# 08_FPGA_banks_3_4_5.net
KiCad netlist of a schematic drawn in Altium Designer
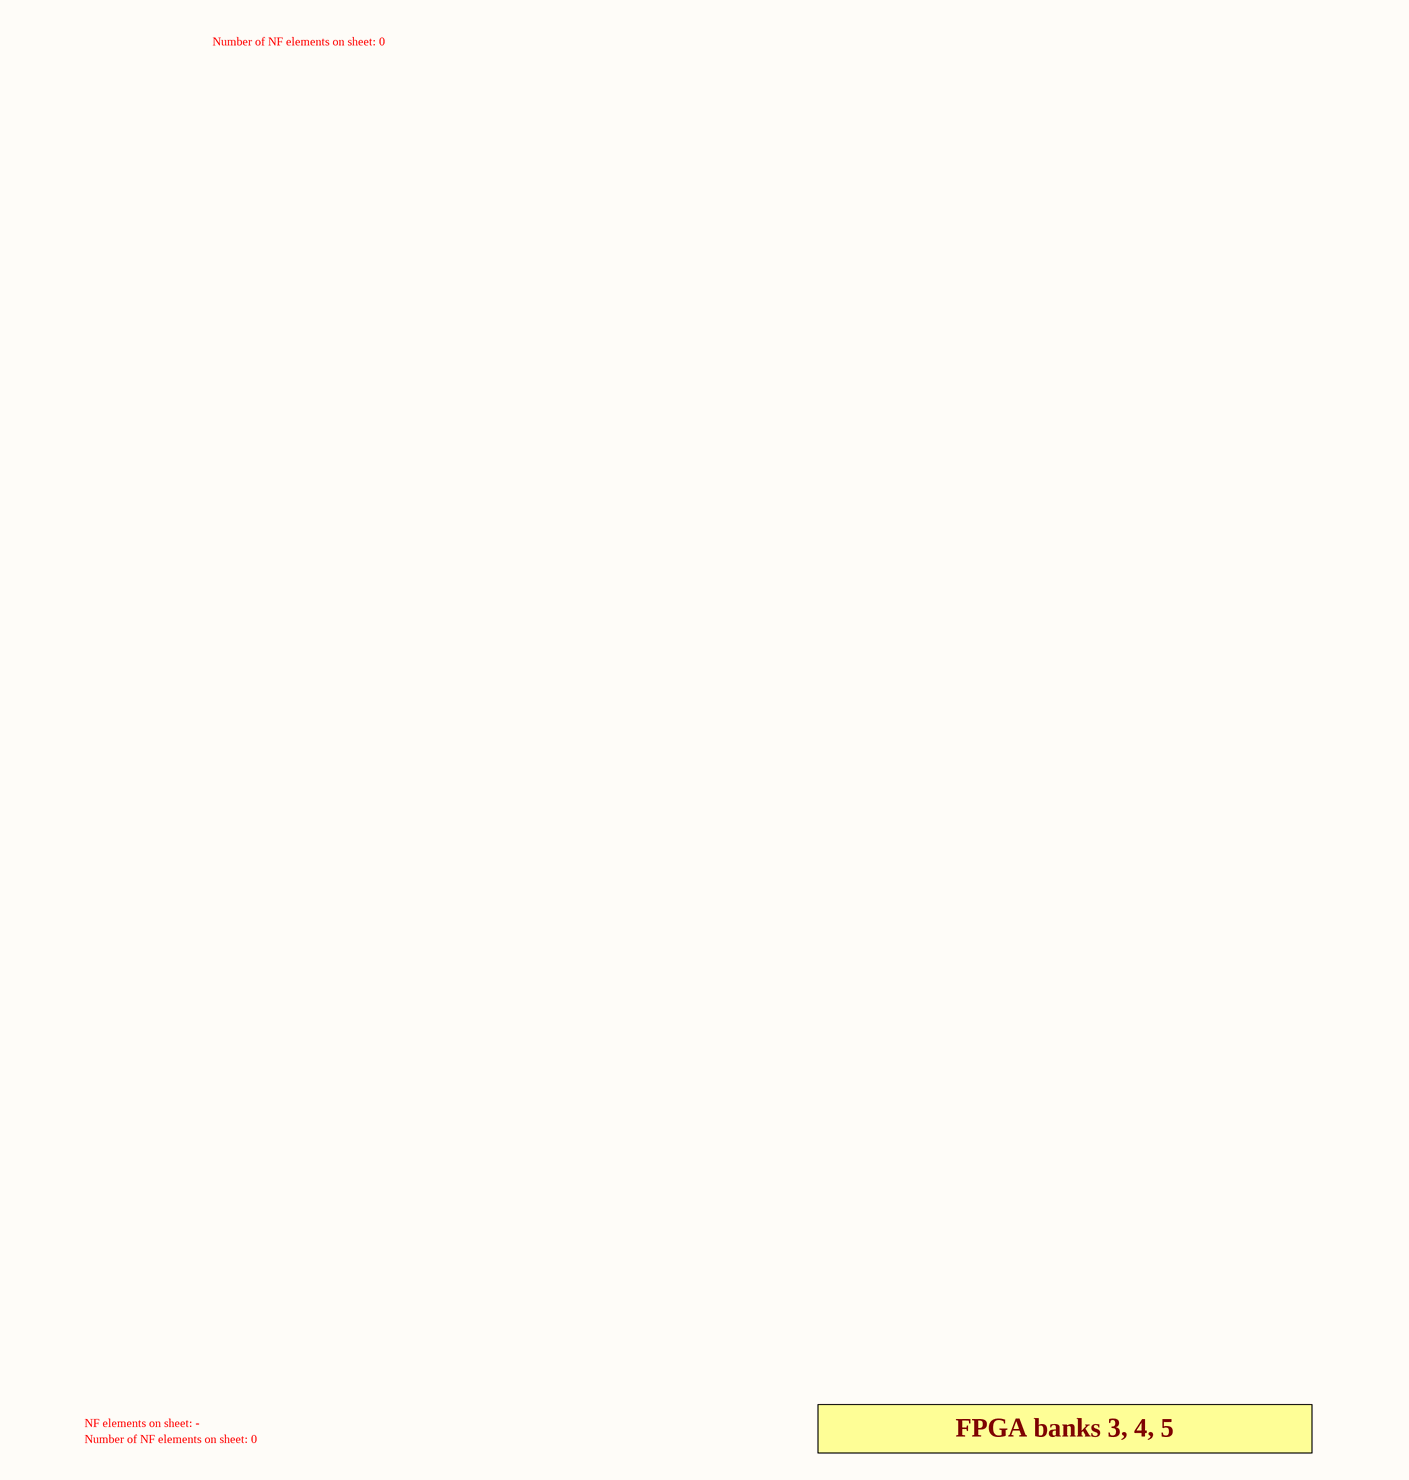
[diagram p0: 08_FPGA_banks_3_4_5.SchDoc, top]
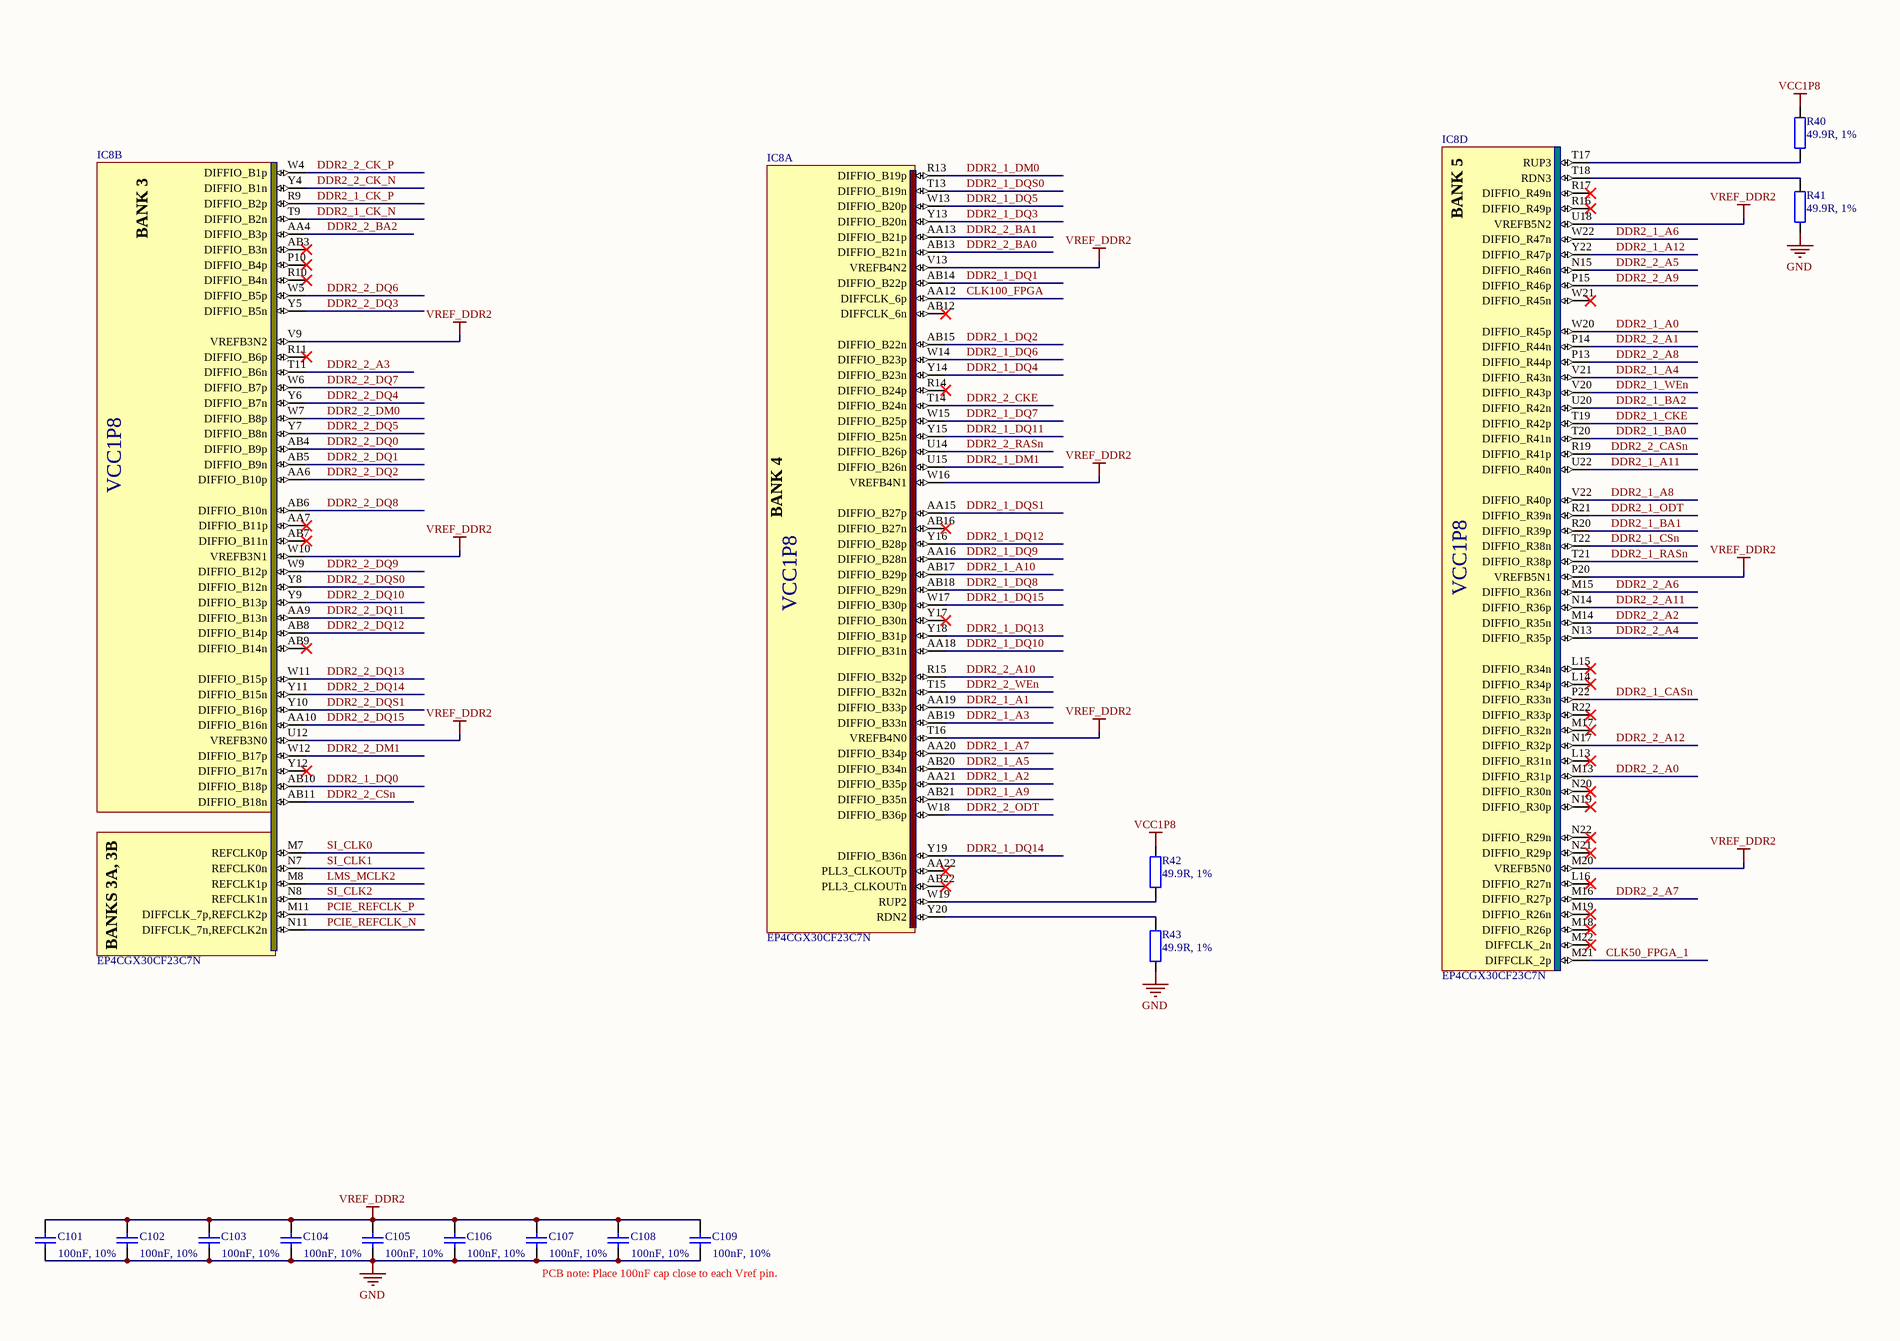
[diagram p1: 08_FPGA_banks_3_4_5.SchDoc, bottom]

(export (version "E")
  (design (tool "Eeschema 10.0.6"))
  (components
    (comp (ref "C101")
      (value "100nF, 10%")
      (footprint "CAP0402")
      (fields
        (field (name "TOLERANCE") "10 %")
        (field (name "MANUFACTURER") "Murata Electronics")
        (field (name "MANUFACTURER PART NUMBER") "GRM155R71C104KA88D")
      )
      (libsource (lib "LimeFPGAboard_schLib") (part "Cap_0603"))
    )
    (comp (ref "C102")
      (value "100nF, 10%")
      (footprint "CAP0402")
      (fields
        (field (name "TOLERANCE") "10 %")
        (field (name "MANUFACTURER") "Murata Electronics")
        (field (name "MANUFACTURER PART NUMBER") "GRM155R71C104KA88D")
      )
      (libsource (lib "LimeFPGAboard_schLib") (part "Cap_0603"))
    )
    (comp (ref "C103")
      (value "100nF, 10%")
      (footprint "CAP0402")
      (fields
        (field (name "TOLERANCE") "10 %")
        (field (name "MANUFACTURER") "Murata Electronics")
        (field (name "MANUFACTURER PART NUMBER") "GRM155R71C104KA88D")
      )
      (libsource (lib "LimeFPGAboard_schLib") (part "Cap_0603"))
    )
    (comp (ref "C104")
      (value "100nF, 10%")
      (footprint "CAP0402")
      (fields
        (field (name "TOLERANCE") "10 %")
        (field (name "MANUFACTURER") "Murata Electronics")
        (field (name "MANUFACTURER PART NUMBER") "GRM155R71C104KA88D")
      )
      (libsource (lib "LimeFPGAboard_schLib") (part "Cap_0603"))
    )
    (comp (ref "C105")
      (value "100nF, 10%")
      (footprint "CAP0402")
      (fields
        (field (name "TOLERANCE") "10 %")
        (field (name "MANUFACTURER") "Murata Electronics")
        (field (name "MANUFACTURER PART NUMBER") "GRM155R71C104KA88D")
      )
      (libsource (lib "LimeFPGAboard_schLib") (part "Cap_0603"))
    )
    (comp (ref "C106")
      (value "100nF, 10%")
      (footprint "CAP0402")
      (fields
        (field (name "TOLERANCE") "10 %")
        (field (name "MANUFACTURER") "Murata Electronics")
        (field (name "MANUFACTURER PART NUMBER") "GRM155R71C104KA88D")
      )
      (libsource (lib "LimeFPGAboard_schLib") (part "Cap_0603"))
    )
    (comp (ref "C107")
      (value "100nF, 10%")
      (footprint "CAP0402")
      (fields
        (field (name "TOLERANCE") "10 %")
        (field (name "MANUFACTURER") "Murata Electronics")
        (field (name "MANUFACTURER PART NUMBER") "GRM155R71C104KA88D")
      )
      (libsource (lib "LimeFPGAboard_schLib") (part "Cap_0603"))
    )
    (comp (ref "C108")
      (value "100nF, 10%")
      (footprint "CAP0402")
      (fields
        (field (name "TOLERANCE") "10 %")
        (field (name "MANUFACTURER") "Murata Electronics")
        (field (name "MANUFACTURER PART NUMBER") "GRM155R71C104KA88D")
      )
      (libsource (lib "LimeFPGAboard_schLib") (part "Cap_0603"))
    )
    (comp (ref "C109")
      (value "100nF, 10%")
      (footprint "CAP0402")
      (fields
        (field (name "TOLERANCE") "10 %")
        (field (name "MANUFACTURER") "Murata Electronics")
        (field (name "MANUFACTURER PART NUMBER") "GRM155R71C104KA88D")
      )
      (libsource (lib "LimeFPGAboard_schLib") (part "Cap_0603"))
    )
    (comp (ref "IC8")
      (value "EP4CGX30CF23C7N")
      (footprint "ALTR-FBGA484_A-200")
      (fields (field (name "MANUFACTURER") "Altera"))
      (libsource (lib "LimeMicroAltiumLib_schLib") (part "EP4CGX30CF23C7N"))
    )
    (comp (ref "R40")
      (value "49.9R, 1%")
      (footprint "RES0402")
      (fields
        (field (name "TOLERANCE") "±1%")
        (field (name "MANUFACTURER") "Samsung Electro-Mechanics America, Inc.")
        (field (name "MANUFACTURER PART NUMBER") "RC1005F49R9CS")
      )
      (libsource (lib "LimeMicroAltiumLib_schLib") (part "Res_0402"))
    )
    (comp (ref "R41")
      (value "49.9R, 1%")
      (footprint "RES0402")
      (fields
        (field (name "TOLERANCE") "±1%")
        (field (name "MANUFACTURER") "Samsung Electro-Mechanics America, Inc.")
        (field (name "MANUFACTURER PART NUMBER") "RC1005F49R9CS")
      )
      (libsource (lib "LimeMicroAltiumLib_schLib") (part "Res_0402"))
    )
    (comp (ref "R42")
      (value "49.9R, 1%")
      (footprint "RES0402")
      (fields
        (field (name "TOLERANCE") "±1%")
        (field (name "MANUFACTURER") "Samsung Electro-Mechanics America, Inc.")
        (field (name "MANUFACTURER PART NUMBER") "RC1005F49R9CS")
      )
      (libsource (lib "LimeMicroAltiumLib_schLib") (part "Res_0402"))
    )
    (comp (ref "R43")
      (value "49.9R, 1%")
      (footprint "RES0402")
      (fields
        (field (name "TOLERANCE") "±1%")
        (field (name "MANUFACTURER") "Samsung Electro-Mechanics America, Inc.")
        (field (name "MANUFACTURER PART NUMBER") "RC1005F49R9CS")
      )
      (libsource (lib "LimeMicroAltiumLib_schLib") (part "Res_0402"))
    )
  )
  (nets
    (net (code "1") (name "/CLK50_FPGA_1") (class "Default")
      (node (ref "IC8") (pin "M21") (pinfunction "DIFFCLK_2p_M21") (pintype "bidirectional"))
    )
    (net (code "2") (name "/CLK100_FPGA") (class "Default")
      (node (ref "IC8") (pin "AA12") (pinfunction "DIFFCLK_6p_AA12") (pintype "bidirectional"))
    )
    (net (code "3") (name "/DDR2_1_A0") (class "Default")
      (node (ref "IC8") (pin "W20") (pinfunction "DIFFIO_R45p_W20") (pintype "bidirectional"))
    )
    (net (code "4") (name "/DDR2_1_A1") (class "Default")
      (node (ref "IC8") (pin "AA19") (pinfunction "DIFFIO_B33p_AA19") (pintype "bidirectional"))
    )
    (net (code "5") (name "/DDR2_1_A2") (class "Default")
      (node (ref "IC8") (pin "AA21") (pinfunction "DIFFIO_B35p_AA21") (pintype "bidirectional"))
    )
    (net (code "6") (name "/DDR2_1_A3") (class "Default")
      (node (ref "IC8") (pin "AB19") (pinfunction "DIFFIO_B33n_AB19") (pintype "bidirectional"))
    )
    (net (code "7") (name "/DDR2_1_A4") (class "Default")
      (node (ref "IC8") (pin "V21") (pinfunction "DIFFIO_R43n_V21") (pintype "bidirectional"))
    )
    (net (code "8") (name "/DDR2_1_A5") (class "Default")
      (node (ref "IC8") (pin "AB20") (pinfunction "DIFFIO_B34n_AB20") (pintype "bidirectional"))
    )
    (net (code "9") (name "/DDR2_1_A6") (class "Default")
      (node (ref "IC8") (pin "W22") (pinfunction "DIFFIO_R47n_W22") (pintype "bidirectional"))
    )
    (net (code "10") (name "/DDR2_1_A7") (class "Default")
      (node (ref "IC8") (pin "AA20") (pinfunction "DIFFIO_B34p_AA20") (pintype "bidirectional"))
    )
    (net (code "11") (name "/DDR2_1_A8") (class "Default")
      (node (ref "IC8") (pin "V22") (pinfunction "DIFFIO_R40p_V22") (pintype "bidirectional"))
    )
    (net (code "12") (name "/DDR2_1_A9") (class "Default")
      (node (ref "IC8") (pin "AB21") (pinfunction "DIFFIO_B35n_AB21") (pintype "bidirectional"))
    )
    (net (code "13") (name "/DDR2_1_A10") (class "Default")
      (node (ref "IC8") (pin "AB17") (pinfunction "DIFFIO_B29p_AB17") (pintype "bidirectional"))
    )
    (net (code "14") (name "/DDR2_1_A11") (class "Default")
      (node (ref "IC8") (pin "U22") (pinfunction "DIFFIO_R40n_U22") (pintype "bidirectional"))
    )
    (net (code "15") (name "/DDR2_1_A12") (class "Default")
      (node (ref "IC8") (pin "Y22") (pinfunction "DIFFIO_R47p_Y22") (pintype "bidirectional"))
    )
    (net (code "16") (name "/DDR2_1_BA0") (class "Default")
      (node (ref "IC8") (pin "T20") (pinfunction "DIFFIO_R41n_T20") (pintype "bidirectional"))
    )
    (net (code "17") (name "/DDR2_1_BA1") (class "Default")
      (node (ref "IC8") (pin "R20") (pinfunction "DIFFIO_R39p_R20") (pintype "bidirectional"))
    )
    (net (code "18") (name "/DDR2_1_BA2") (class "Default")
      (node (ref "IC8") (pin "U20") (pinfunction "DIFFIO_R42n_U20") (pintype "bidirectional"))
    )
    (net (code "19") (name "/DDR2_1_CASn") (class "Default")
      (node (ref "IC8") (pin "P22") (pinfunction "DIFFIO_R33n_P22") (pintype "bidirectional"))
    )
    (net (code "20") (name "/DDR2_1_CKE") (class "Default")
      (node (ref "IC8") (pin "T19") (pinfunction "DIFFIO_R42p_T19") (pintype "bidirectional"))
    )
    (net (code "21") (name "/DDR2_1_CK_N") (class "Default")
      (node (ref "IC8") (pin "T9") (pinfunction "DIFFIO_B2n_T9") (pintype "bidirectional"))
    )
    (net (code "22") (name "/DDR2_1_CK_P") (class "Default")
      (node (ref "IC8") (pin "R9") (pinfunction "DIFFIO_B2p_R9") (pintype "bidirectional"))
    )
    (net (code "23") (name "/DDR2_1_CSn") (class "Default")
      (node (ref "IC8") (pin "T22") (pinfunction "DIFFIO_R38n_T22") (pintype "bidirectional"))
    )
    (net (code "24") (name "/DDR2_1_DM0") (class "Default")
      (node (ref "IC8") (pin "R13") (pinfunction "DIFFIO_B19p_R13") (pintype "bidirectional"))
    )
    (net (code "25") (name "/DDR2_1_DM1") (class "Default")
      (node (ref "IC8") (pin "U15") (pinfunction "DIFFIO_B26n_U15") (pintype "bidirectional"))
    )
    (net (code "26") (name "/DDR2_1_DQ0") (class "Default")
      (node (ref "IC8") (pin "AB10") (pinfunction "DIFFIO_B18p_AB10") (pintype "bidirectional"))
    )
    (net (code "27") (name "/DDR2_1_DQ1") (class "Default")
      (node (ref "IC8") (pin "AB14") (pinfunction "DIFFIO_B22p_AB14") (pintype "bidirectional"))
    )
    (net (code "28") (name "/DDR2_1_DQ2") (class "Default")
      (node (ref "IC8") (pin "AB15") (pinfunction "DIFFIO_B22n_AB15") (pintype "bidirectional"))
    )
    (net (code "29") (name "/DDR2_1_DQ3") (class "Default")
      (node (ref "IC8") (pin "Y13") (pinfunction "DIFFIO_B20n_Y13") (pintype "bidirectional"))
    )
    (net (code "30") (name "/DDR2_1_DQ4") (class "Default")
      (node (ref "IC8") (pin "Y14") (pinfunction "DIFFIO_B23n_Y14") (pintype "bidirectional"))
    )
    (net (code "31") (name "/DDR2_1_DQ5") (class "Default")
      (node (ref "IC8") (pin "W13") (pinfunction "DIFFIO_B20p_W13") (pintype "bidirectional"))
    )
    (net (code "32") (name "/DDR2_1_DQ6") (class "Default")
      (node (ref "IC8") (pin "W14") (pinfunction "DIFFIO_B23p_W14") (pintype "bidirectional"))
    )
    (net (code "33") (name "/DDR2_1_DQ7") (class "Default")
      (node (ref "IC8") (pin "W15") (pinfunction "DIFFIO_B25p_W15") (pintype "bidirectional"))
    )
    (net (code "34") (name "/DDR2_1_DQ8") (class "Default")
      (node (ref "IC8") (pin "AB18") (pinfunction "DIFFIO_B29n_AB18") (pintype "bidirectional"))
    )
    (net (code "35") (name "/DDR2_1_DQ9") (class "Default")
      (node (ref "IC8") (pin "AA16") (pinfunction "DIFFIO_B28n_AA16") (pintype "bidirectional"))
    )
    (net (code "36") (name "/DDR2_1_DQ10") (class "Default")
      (node (ref "IC8") (pin "AA18") (pinfunction "DIFFIO_B31n_AA18") (pintype "bidirectional"))
    )
    (net (code "37") (name "/DDR2_1_DQ11") (class "Default")
      (node (ref "IC8") (pin "Y15") (pinfunction "DIFFIO_B25n_Y15") (pintype "bidirectional"))
    )
    (net (code "38") (name "/DDR2_1_DQ12") (class "Default")
      (node (ref "IC8") (pin "Y16") (pinfunction "DIFFIO_B28p_Y16") (pintype "bidirectional"))
    )
    (net (code "39") (name "/DDR2_1_DQ13") (class "Default")
      (node (ref "IC8") (pin "Y18") (pinfunction "DIFFIO_B31p_Y18") (pintype "bidirectional"))
    )
    (net (code "40") (name "/DDR2_1_DQ14") (class "Default")
      (node (ref "IC8") (pin "Y19") (pinfunction "DIFFIO_B36n_Y19") (pintype "bidirectional"))
    )
    (net (code "41") (name "/DDR2_1_DQ15") (class "Default")
      (node (ref "IC8") (pin "W17") (pinfunction "DIFFIO_B30p_W17") (pintype "bidirectional"))
    )
    (net (code "42") (name "/DDR2_1_DQS0") (class "Default")
      (node (ref "IC8") (pin "T13") (pinfunction "DIFFIO_B19n_T13") (pintype "bidirectional"))
    )
    (net (code "43") (name "/DDR2_1_DQS1") (class "Default")
      (node (ref "IC8") (pin "AA15") (pinfunction "DIFFIO_B27p_AA15") (pintype "bidirectional"))
    )
    (net (code "44") (name "/DDR2_1_ODT") (class "Default")
      (node (ref "IC8") (pin "R21") (pinfunction "DIFFIO_R39n_R21") (pintype "bidirectional"))
    )
    (net (code "45") (name "/DDR2_1_RASn") (class "Default")
      (node (ref "IC8") (pin "T21") (pinfunction "DIFFIO_R38p_T21") (pintype "bidirectional"))
    )
    (net (code "46") (name "/DDR2_1_WEn") (class "Default")
      (node (ref "IC8") (pin "V20") (pinfunction "DIFFIO_R43p_V20") (pintype "bidirectional"))
    )
    (net (code "47") (name "/DDR2_2_A0") (class "Default")
      (node (ref "IC8") (pin "M13") (pinfunction "DIFFIO_R31p_M13") (pintype "bidirectional"))
    )
    (net (code "48") (name "/DDR2_2_A1") (class "Default")
      (node (ref "IC8") (pin "P14") (pinfunction "DIFFIO_R44n_P14") (pintype "bidirectional"))
    )
    (net (code "49") (name "/DDR2_2_A2") (class "Default")
      (node (ref "IC8") (pin "M14") (pinfunction "DIFFIO_R35n_M14") (pintype "bidirectional"))
    )
    (net (code "50") (name "/DDR2_2_A3") (class "Default")
      (node (ref "IC8") (pin "T11") (pinfunction "DIFFIO_B6n_T11") (pintype "bidirectional"))
    )
    (net (code "51") (name "/DDR2_2_A4") (class "Default")
      (node (ref "IC8") (pin "N13") (pinfunction "DIFFIO_R35p_N13") (pintype "bidirectional"))
    )
    (net (code "52") (name "/DDR2_2_A5") (class "Default")
      (node (ref "IC8") (pin "N15") (pinfunction "DIFFIO_R46n_N15") (pintype "bidirectional"))
    )
    (net (code "53") (name "/DDR2_2_A6") (class "Default")
      (node (ref "IC8") (pin "M15") (pinfunction "DIFFIO_R36n_M15") (pintype "bidirectional"))
    )
    (net (code "54") (name "/DDR2_2_A7") (class "Default")
      (node (ref "IC8") (pin "M16") (pinfunction "DIFFIO_R27p_M16") (pintype "bidirectional"))
    )
    (net (code "55") (name "/DDR2_2_A8") (class "Default")
      (node (ref "IC8") (pin "P13") (pinfunction "DIFFIO_R44p_P13") (pintype "bidirectional"))
    )
    (net (code "56") (name "/DDR2_2_A9") (class "Default")
      (node (ref "IC8") (pin "P15") (pinfunction "DIFFIO_R46p_P15") (pintype "bidirectional"))
    )
    (net (code "57") (name "/DDR2_2_A10") (class "Default")
      (node (ref "IC8") (pin "R15") (pinfunction "DIFFIO_B32p_R15") (pintype "bidirectional"))
    )
    (net (code "58") (name "/DDR2_2_A11") (class "Default")
      (node (ref "IC8") (pin "N14") (pinfunction "DIFFIO_R36p_N14") (pintype "bidirectional"))
    )
    (net (code "59") (name "/DDR2_2_A12") (class "Default")
      (node (ref "IC8") (pin "N17") (pinfunction "DIFFIO_R32p_N17") (pintype "bidirectional"))
    )
    (net (code "60") (name "/DDR2_2_BA0") (class "Default")
      (node (ref "IC8") (pin "AB13") (pinfunction "DIFFIO_B21n_AB13") (pintype "bidirectional"))
    )
    (net (code "61") (name "/DDR2_2_BA1") (class "Default")
      (node (ref "IC8") (pin "AA13") (pinfunction "DIFFIO_B21p_AA13") (pintype "bidirectional"))
    )
    (net (code "62") (name "/DDR2_2_BA2") (class "Default")
      (node (ref "IC8") (pin "AA4") (pinfunction "DIFFIO_B3p_AA4") (pintype "bidirectional"))
    )
    (net (code "63") (name "/DDR2_2_CASn") (class "Default")
      (node (ref "IC8") (pin "R19") (pinfunction "DIFFIO_R41p_R19") (pintype "bidirectional"))
    )
    (net (code "64") (name "/DDR2_2_CKE") (class "Default")
      (node (ref "IC8") (pin "T14") (pinfunction "DIFFIO_B24n_T14") (pintype "bidirectional"))
    )
    (net (code "65") (name "/DDR2_2_CK_N") (class "Default")
      (node (ref "IC8") (pin "Y4") (pinfunction "DIFFIO_B1n_Y4") (pintype "bidirectional"))
    )
    (net (code "66") (name "/DDR2_2_CK_P") (class "Default")
      (node (ref "IC8") (pin "W4") (pinfunction "DIFFIO_B1p_W4") (pintype "bidirectional"))
    )
    (net (code "67") (name "/DDR2_2_CSn") (class "Default")
      (node (ref "IC8") (pin "AB11") (pinfunction "DIFFIO_B18n_AB11") (pintype "bidirectional"))
    )
    (net (code "68") (name "/DDR2_2_DM0") (class "Default")
      (node (ref "IC8") (pin "W7") (pinfunction "DIFFIO_B8p_W7") (pintype "bidirectional"))
    )
    (net (code "69") (name "/DDR2_2_DM1") (class "Default")
      (node (ref "IC8") (pin "W12") (pinfunction "DIFFIO_B17p_W12") (pintype "bidirectional"))
    )
    (net (code "70") (name "/DDR2_2_DQ0") (class "Default")
      (node (ref "IC8") (pin "AB4") (pinfunction "DIFFIO_B9p_AB4") (pintype "bidirectional"))
    )
    (net (code "71") (name "/DDR2_2_DQ1") (class "Default")
      (node (ref "IC8") (pin "AB5") (pinfunction "DIFFIO_B9n_AB5") (pintype "bidirectional"))
    )
    (net (code "72") (name "/DDR2_2_DQ2") (class "Default")
      (node (ref "IC8") (pin "AA6") (pinfunction "DIFFIO_B10p_AA6") (pintype "bidirectional"))
    )
    (net (code "73") (name "/DDR2_2_DQ3") (class "Default")
      (node (ref "IC8") (pin "Y5") (pinfunction "DIFFIO_B5n_Y5") (pintype "bidirectional"))
    )
    (net (code "74") (name "/DDR2_2_DQ4") (class "Default")
      (node (ref "IC8") (pin "Y6") (pinfunction "DIFFIO_B7n_Y6") (pintype "bidirectional"))
    )
    (net (code "75") (name "/DDR2_2_DQ5") (class "Default")
      (node (ref "IC8") (pin "Y7") (pinfunction "DIFFIO_B8n_Y7") (pintype "bidirectional"))
    )
    (net (code "76") (name "/DDR2_2_DQ6") (class "Default")
      (node (ref "IC8") (pin "W5") (pinfunction "DIFFIO_B5p_W5") (pintype "bidirectional"))
    )
    (net (code "77") (name "/DDR2_2_DQ7") (class "Default")
      (node (ref "IC8") (pin "W6") (pinfunction "DIFFIO_B7p_W6") (pintype "bidirectional"))
    )
    (net (code "78") (name "/DDR2_2_DQ8") (class "Default")
      (node (ref "IC8") (pin "AB6") (pinfunction "DIFFIO_B10n_AB6") (pintype "bidirectional"))
    )
    (net (code "79") (name "/DDR2_2_DQ9") (class "Default")
      (node (ref "IC8") (pin "W9") (pinfunction "DIFFIO_B12p_W9") (pintype "bidirectional"))
    )
    (net (code "80") (name "/DDR2_2_DQ10") (class "Default")
      (node (ref "IC8") (pin "Y9") (pinfunction "DIFFIO_B13p_Y9") (pintype "bidirectional"))
    )
    (net (code "81") (name "/DDR2_2_DQ11") (class "Default")
      (node (ref "IC8") (pin "AA9") (pinfunction "DIFFIO_B13n_AA9") (pintype "bidirectional"))
    )
    (net (code "82") (name "/DDR2_2_DQ12") (class "Default")
      (node (ref "IC8") (pin "AB8") (pinfunction "DIFFIO_B14p_AB8") (pintype "bidirectional"))
    )
    (net (code "83") (name "/DDR2_2_DQ13") (class "Default")
      (node (ref "IC8") (pin "W11") (pinfunction "DIFFIO_B15p_W11") (pintype "bidirectional"))
    )
    (net (code "84") (name "/DDR2_2_DQ14") (class "Default")
      (node (ref "IC8") (pin "Y11") (pinfunction "DIFFIO_B15n_Y11") (pintype "bidirectional"))
    )
    (net (code "85") (name "/DDR2_2_DQ15") (class "Default")
      (node (ref "IC8") (pin "AA10") (pinfunction "DIFFIO_B16n_AA10") (pintype "bidirectional"))
    )
    (net (code "86") (name "/DDR2_2_DQS0") (class "Default")
      (node (ref "IC8") (pin "Y8") (pinfunction "DIFFIO_B12n_Y8") (pintype "bidirectional"))
    )
    (net (code "87") (name "/DDR2_2_DQS1") (class "Default")
      (node (ref "IC8") (pin "Y10") (pinfunction "DIFFIO_B16p_Y10") (pintype "bidirectional"))
    )
    (net (code "88") (name "/DDR2_2_ODT") (class "Default")
      (node (ref "IC8") (pin "W18") (pinfunction "DIFFIO_B36p_W18") (pintype "bidirectional"))
    )
    (net (code "89") (name "/DDR2_2_RASn") (class "Default")
      (node (ref "IC8") (pin "U14") (pinfunction "DIFFIO_B26p_U14") (pintype "bidirectional"))
    )
    (net (code "90") (name "/DDR2_2_WEn") (class "Default")
      (node (ref "IC8") (pin "T15") (pinfunction "DIFFIO_B32n_T15") (pintype "bidirectional"))
    )
    (net (code "91") (name "/LMS_MCLK2") (class "Default")
      (node (ref "IC8") (pin "M8") (pinfunction "REFCLK1p_M8") (pintype "bidirectional"))
    )
    (net (code "92") (name "/PCIE_REFCLK_N") (class "Default")
      (node (ref "IC8") (pin "N11") (pinfunction "DIFFCLK_7n,REFCLK2n_N11") (pintype "bidirectional"))
    )
    (net (code "93") (name "/PCIE_REFCLK_P") (class "Default")
      (node (ref "IC8") (pin "M11") (pinfunction "DIFFCLK_7p,REFCLK2p_M11") (pintype "bidirectional"))
    )
    (net (code "94") (name "/SI_CLK0") (class "Default")
      (node (ref "IC8") (pin "M7") (pinfunction "REFCLK0p_M7") (pintype "bidirectional"))
    )
    (net (code "95") (name "/SI_CLK1") (class "Default")
      (node (ref "IC8") (pin "N7") (pinfunction "REFCLK0n_N7") (pintype "bidirectional"))
    )
    (net (code "96") (name "/SI_CLK2") (class "Default")
      (node (ref "IC8") (pin "N8") (pinfunction "REFCLK1n_N8") (pintype "bidirectional"))
    )
    (net (code "97") (name "GND") (class "Default")
      (node (ref "C101") (pin "2") (pinfunction "2_2") (pintype "passive"))
      (node (ref "C102") (pin "2") (pinfunction "2_2") (pintype "passive"))
      (node (ref "C103") (pin "2") (pinfunction "2_2") (pintype "passive"))
      (node (ref "C104") (pin "2") (pinfunction "2_2") (pintype "passive"))
      (node (ref "C105") (pin "2") (pinfunction "2_2") (pintype "passive"))
      (node (ref "C106") (pin "2") (pinfunction "2_2") (pintype "passive"))
      (node (ref "C107") (pin "2") (pinfunction "2_2") (pintype "passive"))
      (node (ref "C108") (pin "2") (pinfunction "2_2") (pintype "passive"))
      (node (ref "C109") (pin "2") (pinfunction "2_2") (pintype "passive"))
      (node (ref "R41") (pin "1") (pinfunction "1_1") (pintype "passive"))
      (node (ref "R43") (pin "1") (pinfunction "1_1") (pintype "passive"))
    )
    (net (code "98") (name "Net-(IC8A-RDN2)") (class "Default")
      (node (ref "IC8") (pin "Y20") (pinfunction "RDN2_Y20") (pintype "bidirectional"))
      (node (ref "R43") (pin "2") (pinfunction "2_2") (pintype "passive"))
    )
    (net (code "99") (name "Net-(IC8A-RUP2)") (class "Default")
      (node (ref "IC8") (pin "W19") (pinfunction "RUP2_W19") (pintype "bidirectional"))
      (node (ref "R42") (pin "1") (pinfunction "1_1") (pintype "passive"))
    )
    (net (code "100") (name "Net-(IC8D-RDN3)") (class "Default")
      (node (ref "IC8") (pin "T18") (pinfunction "RDN3_T18") (pintype "bidirectional"))
      (node (ref "R41") (pin "2") (pinfunction "2_2") (pintype "passive"))
    )
    (net (code "101") (name "Net-(IC8D-RUP3)") (class "Default")
      (node (ref "IC8") (pin "T17") (pinfunction "RUP3_T17") (pintype "bidirectional"))
      (node (ref "R40") (pin "1") (pinfunction "1_1") (pintype "passive"))
    )
    (net (code "102") (name "VCC1P8") (class "Default")
      (node (ref "R40") (pin "2") (pinfunction "2_2") (pintype "passive"))
      (node (ref "R42") (pin "2") (pinfunction "2_2") (pintype "passive"))
    )
    (net (code "103") (name "VREF_DDR2") (class "Default")
      (node (ref "C101") (pin "1") (pinfunction "1_1") (pintype "passive"))
      (node (ref "C102") (pin "1") (pinfunction "1_1") (pintype "passive"))
      (node (ref "C103") (pin "1") (pinfunction "1_1") (pintype "passive"))
      (node (ref "C104") (pin "1") (pinfunction "1_1") (pintype "passive"))
      (node (ref "C105") (pin "1") (pinfunction "1_1") (pintype "passive"))
      (node (ref "C106") (pin "1") (pinfunction "1_1") (pintype "passive"))
      (node (ref "C107") (pin "1") (pinfunction "1_1") (pintype "passive"))
      (node (ref "C108") (pin "1") (pinfunction "1_1") (pintype "passive"))
      (node (ref "C109") (pin "1") (pinfunction "1_1") (pintype "passive"))
      (node (ref "IC8") (pin "M20") (pinfunction "VREFB5N0_M20") (pintype "bidirectional"))
      (node (ref "IC8") (pin "P20") (pinfunction "VREFB5N1_P20") (pintype "bidirectional"))
      (node (ref "IC8") (pin "T16") (pinfunction "VREFB4N0_T16") (pintype "bidirectional"))
      (node (ref "IC8") (pin "U12") (pinfunction "VREFB3N0_U12") (pintype "bidirectional"))
      (node (ref "IC8") (pin "U18") (pinfunction "VREFB5N2_U18") (pintype "bidirectional"))
      (node (ref "IC8") (pin "V13") (pinfunction "VREFB4N2_V13") (pintype "bidirectional"))
      (node (ref "IC8") (pin "V9") (pinfunction "VREFB3N2_V9") (pintype "bidirectional"))
      (node (ref "IC8") (pin "W10") (pinfunction "VREFB3N1_W10") (pintype "bidirectional"))
      (node (ref "IC8") (pin "W16") (pinfunction "VREFB4N1_W16") (pintype "bidirectional"))
    )
    (net (code "104") (name "unconnected-(IC8A-DIFFCLK_6n-PadAB12)") (class "Default")
      (node (ref "IC8") (pin "AB12") (pinfunction "DIFFCLK_6n_AB12") (pintype "bidirectional+no_connect"))
    )
    (net (code "105") (name "unconnected-(IC8A-DIFFIO_B24p-PadR14)") (class "Default")
      (node (ref "IC8") (pin "R14") (pinfunction "DIFFIO_B24p_R14") (pintype "bidirectional+no_connect"))
    )
    (net (code "106") (name "unconnected-(IC8A-DIFFIO_B27n-PadAB16)") (class "Default")
      (node (ref "IC8") (pin "AB16") (pinfunction "DIFFIO_B27n_AB16") (pintype "bidirectional+no_connect"))
    )
    (net (code "107") (name "unconnected-(IC8A-DIFFIO_B30n-PadY17)") (class "Default")
      (node (ref "IC8") (pin "Y17") (pinfunction "DIFFIO_B30n_Y17") (pintype "bidirectional+no_connect"))
    )
    (net (code "108") (name "unconnected-(IC8A-PLL3_CLKOUTn-PadAB22)") (class "Default")
      (node (ref "IC8") (pin "AB22") (pinfunction "PLL3_CLKOUTn_AB22") (pintype "bidirectional+no_connect"))
    )
    (net (code "109") (name "unconnected-(IC8A-PLL3_CLKOUTp-PadAA22)") (class "Default")
      (node (ref "IC8") (pin "AA22") (pinfunction "PLL3_CLKOUTp_AA22") (pintype "bidirectional+no_connect"))
    )
    (net (code "110") (name "unconnected-(IC8B-DIFFIO_B3n-PadAB3)") (class "Default")
      (node (ref "IC8") (pin "AB3") (pinfunction "DIFFIO_B3n_AB3") (pintype "bidirectional+no_connect"))
    )
    (net (code "111") (name "unconnected-(IC8B-DIFFIO_B4n-PadR10)") (class "Default")
      (node (ref "IC8") (pin "R10") (pinfunction "DIFFIO_B4n_R10") (pintype "bidirectional+no_connect"))
    )
    (net (code "112") (name "unconnected-(IC8B-DIFFIO_B4p-PadP10)") (class "Default")
      (node (ref "IC8") (pin "P10") (pinfunction "DIFFIO_B4p_P10") (pintype "bidirectional+no_connect"))
    )
    (net (code "113") (name "unconnected-(IC8B-DIFFIO_B6p-PadR11)") (class "Default")
      (node (ref "IC8") (pin "R11") (pinfunction "DIFFIO_B6p_R11") (pintype "bidirectional+no_connect"))
    )
    (net (code "114") (name "unconnected-(IC8B-DIFFIO_B11n-PadAB7)") (class "Default")
      (node (ref "IC8") (pin "AB7") (pinfunction "DIFFIO_B11n_AB7") (pintype "bidirectional+no_connect"))
    )
    (net (code "115") (name "unconnected-(IC8B-DIFFIO_B11p-PadAA7)") (class "Default")
      (node (ref "IC8") (pin "AA7") (pinfunction "DIFFIO_B11p_AA7") (pintype "bidirectional+no_connect"))
    )
    (net (code "116") (name "unconnected-(IC8B-DIFFIO_B14n-PadAB9)") (class "Default")
      (node (ref "IC8") (pin "AB9") (pinfunction "DIFFIO_B14n_AB9") (pintype "bidirectional+no_connect"))
    )
    (net (code "117") (name "unconnected-(IC8B-DIFFIO_B17n-PadY12)") (class "Default")
      (node (ref "IC8") (pin "Y12") (pinfunction "DIFFIO_B17n_Y12") (pintype "bidirectional+no_connect"))
    )
    (net (code "118") (name "unconnected-(IC8D-DIFFCLK_2n-PadM22)") (class "Default")
      (node (ref "IC8") (pin "M22") (pinfunction "DIFFCLK_2n_M22") (pintype "bidirectional+no_connect"))
    )
    (net (code "119") (name "unconnected-(IC8D-DIFFIO_R26n-PadM19)") (class "Default")
      (node (ref "IC8") (pin "M19") (pinfunction "DIFFIO_R26n_M19") (pintype "bidirectional+no_connect"))
    )
    (net (code "120") (name "unconnected-(IC8D-DIFFIO_R26p-PadM18)") (class "Default")
      (node (ref "IC8") (pin "M18") (pinfunction "DIFFIO_R26p_M18") (pintype "bidirectional+no_connect"))
    )
    (net (code "121") (name "unconnected-(IC8D-DIFFIO_R27n-PadL16)") (class "Default")
      (node (ref "IC8") (pin "L16") (pinfunction "DIFFIO_R27n_L16") (pintype "bidirectional+no_connect"))
    )
    (net (code "122") (name "unconnected-(IC8D-DIFFIO_R29n-PadN22)") (class "Default")
      (node (ref "IC8") (pin "N22") (pinfunction "DIFFIO_R29n_N22") (pintype "bidirectional+no_connect"))
    )
    (net (code "123") (name "unconnected-(IC8D-DIFFIO_R29p-PadN21)") (class "Default")
      (node (ref "IC8") (pin "N21") (pinfunction "DIFFIO_R29p_N21") (pintype "bidirectional+no_connect"))
    )
    (net (code "124") (name "unconnected-(IC8D-DIFFIO_R30n-PadN20)") (class "Default")
      (node (ref "IC8") (pin "N20") (pinfunction "DIFFIO_R30n_N20") (pintype "bidirectional+no_connect"))
    )
    (net (code "125") (name "unconnected-(IC8D-DIFFIO_R30p-PadN19)") (class "Default")
      (node (ref "IC8") (pin "N19") (pinfunction "DIFFIO_R30p_N19") (pintype "bidirectional+no_connect"))
    )
    (net (code "126") (name "unconnected-(IC8D-DIFFIO_R31n-PadL13)") (class "Default")
      (node (ref "IC8") (pin "L13") (pinfunction "DIFFIO_R31n_L13") (pintype "bidirectional+no_connect"))
    )
    (net (code "127") (name "unconnected-(IC8D-DIFFIO_R32n-PadM17)") (class "Default")
      (node (ref "IC8") (pin "M17") (pinfunction "DIFFIO_R32n_M17") (pintype "bidirectional+no_connect"))
    )
    (net (code "128") (name "unconnected-(IC8D-DIFFIO_R33p-PadR22)") (class "Default")
      (node (ref "IC8") (pin "R22") (pinfunction "DIFFIO_R33p_R22") (pintype "bidirectional+no_connect"))
    )
    (net (code "129") (name "unconnected-(IC8D-DIFFIO_R34n-PadL15)") (class "Default")
      (node (ref "IC8") (pin "L15") (pinfunction "DIFFIO_R34n_L15") (pintype "bidirectional+no_connect"))
    )
    (net (code "130") (name "unconnected-(IC8D-DIFFIO_R34p-PadL14)") (class "Default")
      (node (ref "IC8") (pin "L14") (pinfunction "DIFFIO_R34p_L14") (pintype "bidirectional+no_connect"))
    )
    (net (code "131") (name "unconnected-(IC8D-DIFFIO_R45n-PadW21)") (class "Default")
      (node (ref "IC8") (pin "W21") (pinfunction "DIFFIO_R45n_W21") (pintype "bidirectional+no_connect"))
    )
    (net (code "132") (name "unconnected-(IC8D-DIFFIO_R49n-PadR17)") (class "Default")
      (node (ref "IC8") (pin "R17") (pinfunction "DIFFIO_R49n_R17") (pintype "bidirectional+no_connect"))
    )
    (net (code "133") (name "unconnected-(IC8D-DIFFIO_R49p-PadR16)") (class "Default")
      (node (ref "IC8") (pin "R16") (pinfunction "DIFFIO_R49p_R16") (pintype "bidirectional+no_connect"))
    )
  )
)
